# projeto_1_5.net
KiCad netlist of a schematic drawn in EAGLE
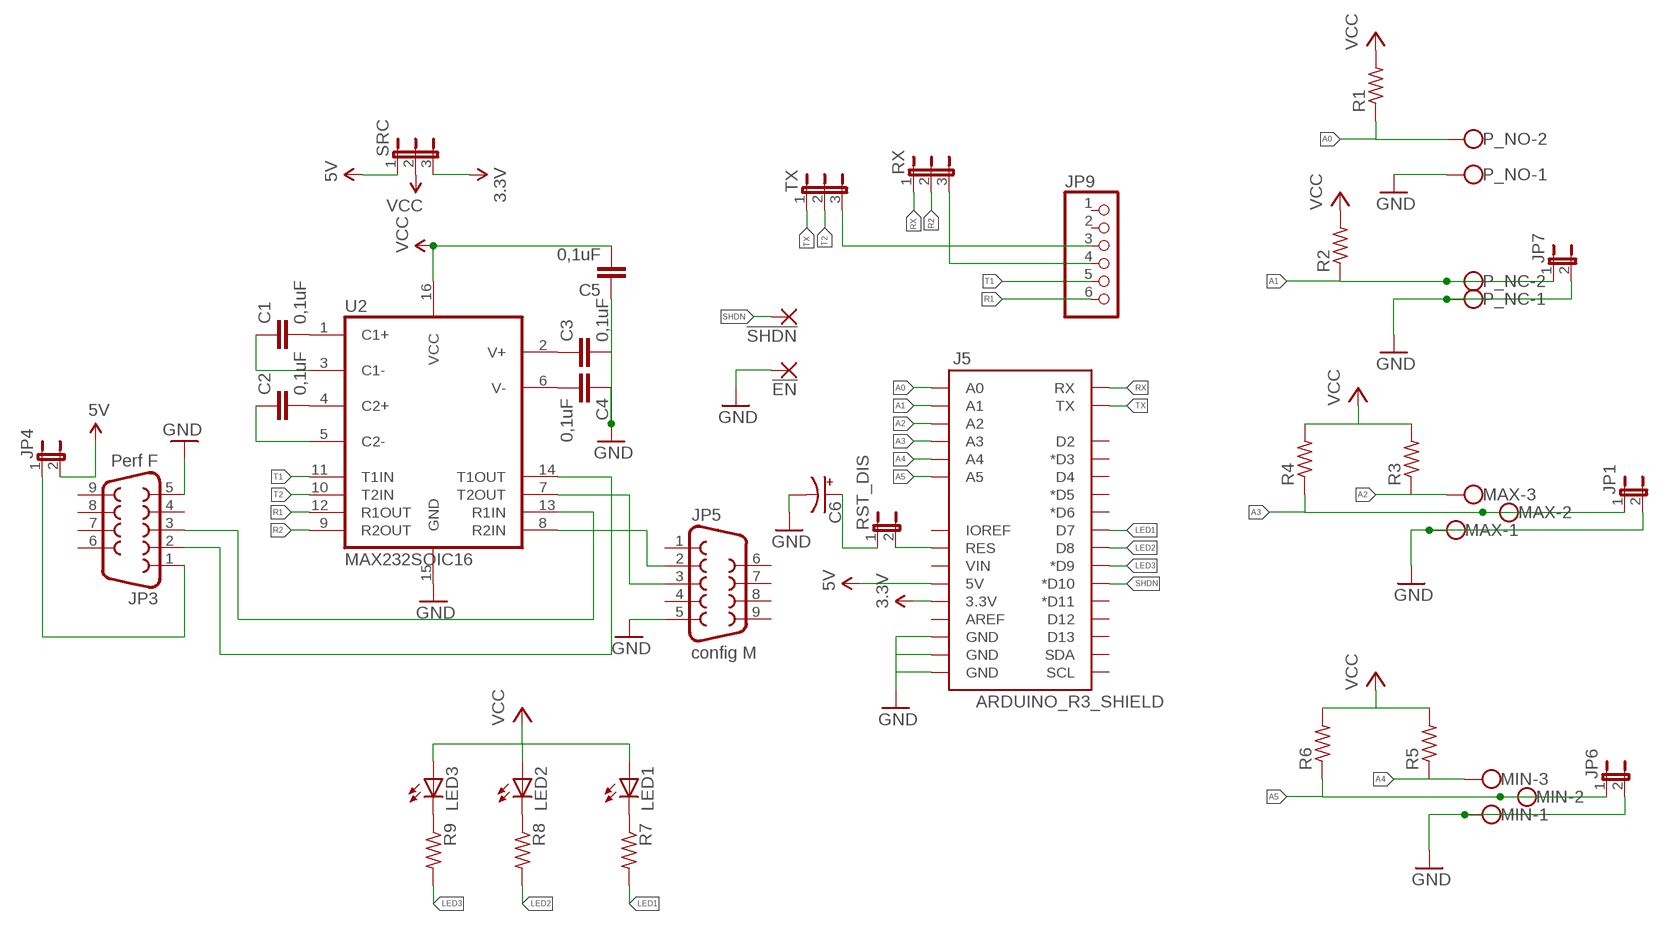
[diagram p0: schematic, sheet 1]

(export (version "E")
  (design (tool "Eeschema 10.0.6"))
  (components
    (comp (ref "!EN")
      (value "SMD2")
      (footprint "eagle-import:SMD1,27-2,54")
      (libsource (lib "eagle-import") (part "SMD2"))
    )
    (comp (ref "!SHDN")
      (value "SMD2")
      (footprint "eagle-import:SMD1,27-2,54")
      (libsource (lib "eagle-import") (part "SMD2"))
    )
    (comp (ref "C1")
      (value "0,1uF")
      (footprint "eagle-import:C0805K")
      (libsource (lib "eagle-import") (part "C-EUC0805K"))
    )
    (comp (ref "C2")
      (value "0,1uF")
      (footprint "eagle-import:C0805K")
      (libsource (lib "eagle-import") (part "C-EUC0805K"))
    )
    (comp (ref "C3")
      (value "0,1uF")
      (footprint "eagle-import:C0805K")
      (libsource (lib "eagle-import") (part "C-EUC0805K"))
    )
    (comp (ref "C4")
      (value "0,1uF")
      (footprint "eagle-import:C0805K")
      (libsource (lib "eagle-import") (part "C-EUC0805K"))
    )
    (comp (ref "C5")
      (value "0,1uF")
      (footprint "eagle-import:C0805K")
      (libsource (lib "eagle-import") (part "C-EUC0805K"))
    )
    (comp (ref "C6")
      (value "CPOL-USTT5D10")
      (footprint "eagle-import:TT5D10")
      (libsource (lib "eagle-import") (part "CPOL-USTT5D10"))
    )
    (comp (ref "J5")
      (value "ARDUINO_R3_SHIELD")
      (footprint "eagle-import:UNO_R3_SHIELD")
      (libsource (lib "eagle-import") (part "ARDUINO_R3_SHIELD"))
    )
    (comp (ref "JP1")
      (value "JP1E")
      (footprint "eagle-import:JP1")
      (libsource (lib "eagle-import") (part "JP1E"))
    )
    (comp (ref "JP3")
      (value "Perf F")
      (footprint "eagle-import:DB9")
      (libsource (lib "eagle-import") (part "DB9FEMALE"))
    )
    (comp (ref "JP4")
      (value "JP1E")
      (footprint "eagle-import:JP1")
      (libsource (lib "eagle-import") (part "JP1E"))
    )
    (comp (ref "JP5")
      (value "config M")
      (footprint "eagle-import:DB9_MALE")
      (libsource (lib "eagle-import") (part "DB9MALE"))
    )
    (comp (ref "JP6")
      (value "JP1E")
      (footprint "eagle-import:JP1")
      (libsource (lib "eagle-import") (part "JP1E"))
    )
    (comp (ref "JP7")
      (value "JP1E")
      (footprint "eagle-import:JP1")
      (libsource (lib "eagle-import") (part "JP1E"))
    )
    (comp (ref "JP9")
      (value "PINHD-1X6")
      (footprint "eagle-import:1X06")
      (libsource (lib "eagle-import") (part "PINHD-1X6"))
    )
    (comp (ref "LED1")
      (value "LED3MM")
      (footprint "eagle-import:LED3MM")
      (libsource (lib "eagle-import") (part "LED3MM"))
    )
    (comp (ref "LED2")
      (value "LED3MM")
      (footprint "eagle-import:LED3MM")
      (libsource (lib "eagle-import") (part "LED3MM"))
    )
    (comp (ref "LED3")
      (value "LED3MM")
      (footprint "eagle-import:LED3MM")
      (libsource (lib "eagle-import") (part "LED3MM"))
    )
    (comp (ref "MAX")
      (value "W237-103")
      (footprint "eagle-import:W237-103")
      (fields (field (name "MPN") "237-103"))
      (libsource (lib "eagle-import") (part "W237-103"))
    )
    (comp (ref "MIN")
      (value "W237-103")
      (footprint "eagle-import:W237-103")
      (fields (field (name "MPN") "237-103"))
      (libsource (lib "eagle-import") (part "W237-103"))
    )
    (comp (ref "P_NC")
      (value "W237-102")
      (footprint "eagle-import:W237-102")
      (fields (field (name "MPN") "237-102"))
      (libsource (lib "eagle-import") (part "W237-102"))
    )
    (comp (ref "P_NO")
      (value "W237-102")
      (footprint "eagle-import:W237-102")
      (fields (field (name "MPN") "237-102"))
      (libsource (lib "eagle-import") (part "W237-102"))
    )
    (comp (ref "R1")
      (value "R-US_R0805")
      (footprint "eagle-import:R0805")
      (libsource (lib "eagle-import") (part "R-US_R0805"))
    )
    (comp (ref "R2")
      (value "R-US_R0805")
      (footprint "eagle-import:R0805")
      (libsource (lib "eagle-import") (part "R-US_R0805"))
    )
    (comp (ref "R3")
      (value "R-US_R0805")
      (footprint "eagle-import:R0805")
      (libsource (lib "eagle-import") (part "R-US_R0805"))
    )
    (comp (ref "R4")
      (value "R-US_R0805")
      (footprint "eagle-import:R0805")
      (libsource (lib "eagle-import") (part "R-US_R0805"))
    )
    (comp (ref "R5")
      (value "R-US_R0805")
      (footprint "eagle-import:R0805")
      (libsource (lib "eagle-import") (part "R-US_R0805"))
    )
    (comp (ref "R6")
      (value "R-US_R0805")
      (footprint "eagle-import:R0805")
      (libsource (lib "eagle-import") (part "R-US_R0805"))
    )
    (comp (ref "R7")
      (value "R-US_R0805")
      (footprint "eagle-import:R0805")
      (libsource (lib "eagle-import") (part "R-US_R0805"))
    )
    (comp (ref "R8")
      (value "R-US_R0805")
      (footprint "eagle-import:R0805")
      (libsource (lib "eagle-import") (part "R-US_R0805"))
    )
    (comp (ref "R9")
      (value "R-US_R0805")
      (footprint "eagle-import:R0805")
      (libsource (lib "eagle-import") (part "R-US_R0805"))
    )
    (comp (ref "RST_DIS")
      (value "JP1E")
      (footprint "eagle-import:JP1")
      (libsource (lib "eagle-import") (part "JP1E"))
    )
    (comp (ref "RX")
      (value "JP2W")
      (footprint "eagle-import:JP2W")
      (libsource (lib "eagle-import") (part "JP2W"))
    )
    (comp (ref "SRC")
      (value "JP2W")
      (footprint "eagle-import:JP2W")
      (libsource (lib "eagle-import") (part "JP2W"))
    )
    (comp (ref "TX")
      (value "JP2W")
      (footprint "eagle-import:JP2W")
      (libsource (lib "eagle-import") (part "JP2W"))
    )
    (comp (ref "U2")
      (value "MAX232SOIC16")
      (footprint "eagle-import:SO016")
      (libsource (lib "eagle-import") (part "MAX232SOIC16"))
    )
  )
  (nets
    (net (code "1") (name "3.3V") (class "Default")
      (node (ref "J5") (pin "3.3V") (pinfunction "3.3V_3.3V") (pintype "bidirectional"))
      (node (ref "SRC") (pin "3") (pinfunction "3_3") (pintype "passive"))
    )
    (net (code "2") (name "5V") (class "Default")
      (node (ref "J5") (pin "5V") (pinfunction "5V_5V") (pintype "bidirectional"))
      (node (ref "JP4") (pin "2") (pinfunction "2_2") (pintype "passive"))
      (node (ref "SRC") (pin "1") (pinfunction "1_1") (pintype "passive"))
    )
    (net (code "3") (name "A0") (class "Default")
      (node (ref "J5") (pin "A0") (pinfunction "A0_A0") (pintype "bidirectional"))
      (node (ref "P_NO") (pin "2") (pinfunction "KL_2") (pintype "passive"))
      (node (ref "R1") (pin "1") (pinfunction "1_1") (pintype "passive"))
    )
    (net (code "4") (name "A1") (class "Default")
      (node (ref "J5") (pin "A1") (pinfunction "A1_A1") (pintype "bidirectional"))
      (node (ref "JP7") (pin "1") (pinfunction "1_1") (pintype "passive"))
      (node (ref "P_NC") (pin "2") (pinfunction "KL_2") (pintype "passive"))
      (node (ref "R2") (pin "1") (pinfunction "1_1") (pintype "passive"))
    )
    (net (code "5") (name "A2") (class "Default")
      (node (ref "J5") (pin "A2") (pinfunction "A2_A2") (pintype "bidirectional"))
      (node (ref "MAX") (pin "3") (pinfunction "KL_3") (pintype "passive"))
      (node (ref "R3") (pin "1") (pinfunction "1_1") (pintype "passive"))
    )
    (net (code "6") (name "A3") (class "Default")
      (node (ref "J5") (pin "A3") (pinfunction "A3_A3") (pintype "bidirectional"))
      (node (ref "JP1") (pin "1") (pinfunction "1_1") (pintype "passive"))
      (node (ref "MAX") (pin "2") (pinfunction "KL_2") (pintype "passive"))
      (node (ref "R4") (pin "1") (pinfunction "1_1") (pintype "passive"))
    )
    (net (code "7") (name "A4") (class "Default")
      (node (ref "J5") (pin "A4") (pinfunction "A4_A4") (pintype "bidirectional"))
      (node (ref "MIN") (pin "3") (pinfunction "KL_3") (pintype "passive"))
      (node (ref "R5") (pin "1") (pinfunction "1_1") (pintype "passive"))
    )
    (net (code "8") (name "A5") (class "Default")
      (node (ref "J5") (pin "A5") (pinfunction "A5_A5") (pintype "bidirectional"))
      (node (ref "JP6") (pin "1") (pinfunction "1_1") (pintype "passive"))
      (node (ref "MIN") (pin "2") (pinfunction "KL_2") (pintype "passive"))
      (node (ref "R6") (pin "1") (pinfunction "1_1") (pintype "passive"))
    )
    (net (code "9") (name "GND") (class "Default")
      (node (ref "!EN") (pin "1") (pinfunction "P_1") (pintype "passive"))
      (node (ref "C3") (pin "2") (pinfunction "2_2") (pintype "passive"))
      (node (ref "C4") (pin "1") (pinfunction "1_1") (pintype "passive"))
      (node (ref "C5") (pin "1") (pinfunction "1_1") (pintype "passive"))
      (node (ref "C6") (pin "-") (pinfunction "-_-") (pintype "passive"))
      (node (ref "J5") (pin "GND@0") (pinfunction "GND_GND@0") (pintype "bidirectional"))
      (node (ref "J5") (pin "GND@1") (pinfunction "GND_GND@1") (pintype "bidirectional"))
      (node (ref "J5") (pin "GND@2") (pinfunction "GND_GND@2") (pintype "bidirectional"))
      (node (ref "JP1") (pin "2") (pinfunction "2_2") (pintype "passive"))
      (node (ref "JP3") (pin "5") (pinfunction "5_5") (pintype "passive"))
      (node (ref "JP5") (pin "5") (pinfunction "5_5") (pintype "passive"))
      (node (ref "JP6") (pin "2") (pinfunction "2_2") (pintype "passive"))
      (node (ref "JP7") (pin "2") (pinfunction "2_2") (pintype "passive"))
      (node (ref "MAX") (pin "1") (pinfunction "KL_1") (pintype "passive"))
      (node (ref "MIN") (pin "1") (pinfunction "KL_1") (pintype "passive"))
      (node (ref "P_NC") (pin "1") (pinfunction "KL_1") (pintype "passive"))
      (node (ref "P_NO") (pin "1") (pinfunction "KL_1") (pintype "passive"))
      (node (ref "U2") (pin "15") (pinfunction "GND_15") (pintype "bidirectional"))
    )
    (net (code "10") (name "LED1") (class "Default")
      (node (ref "J5") (pin "D7") (pinfunction "D7_D7") (pintype "bidirectional"))
      (node (ref "R7") (pin "2") (pinfunction "2_2") (pintype "passive"))
    )
    (net (code "11") (name "LED2") (class "Default")
      (node (ref "J5") (pin "D8") (pinfunction "D8_D8") (pintype "bidirectional"))
      (node (ref "R8") (pin "2") (pinfunction "2_2") (pintype "passive"))
    )
    (net (code "12") (name "LED3") (class "Default")
      (node (ref "J5") (pin "D9") (pinfunction "*D9_D9") (pintype "bidirectional"))
      (node (ref "R9") (pin "2") (pinfunction "2_2") (pintype "passive"))
    )
    (net (code "13") (name "Net-(C6-Pad+)") (class "Default")
      (node (ref "C6") (pin "+") (pinfunction "+_+") (pintype "passive"))
      (node (ref "RST_DIS") (pin "1") (pinfunction "1_1") (pintype "passive"))
    )
    (net (code "14") (name "Net-(J5-PadRES)") (class "Default")
      (node (ref "J5") (pin "RES") (pinfunction "RES_RES") (pintype "bidirectional"))
      (node (ref "RST_DIS") (pin "2") (pinfunction "2_2") (pintype "passive"))
    )
    (net (code "15") (name "Net-(JP3-Pad1)") (class "Default")
      (node (ref "JP3") (pin "1") (pinfunction "1_1") (pintype "passive"))
      (node (ref "JP4") (pin "1") (pinfunction "1_1") (pintype "passive"))
    )
    (net (code "16") (name "Net-(JP9-Pad3)") (class "Default")
      (node (ref "JP9") (pin "3") (pinfunction "3_3") (pintype "passive"))
      (node (ref "TX") (pin "3") (pinfunction "3_3") (pintype "passive"))
    )
    (net (code "17") (name "Net-(JP9-Pad4)") (class "Default")
      (node (ref "JP9") (pin "4") (pinfunction "4_4") (pintype "passive"))
      (node (ref "RX") (pin "3") (pinfunction "3_3") (pintype "passive"))
    )
    (net (code "18") (name "Net-(LED1-C)") (class "Default")
      (node (ref "LED1") (pin "K") (pinfunction "C_K") (pintype "passive"))
      (node (ref "R7") (pin "1") (pinfunction "1_1") (pintype "passive"))
    )
    (net (code "19") (name "Net-(LED2-C)") (class "Default")
      (node (ref "LED2") (pin "K") (pinfunction "C_K") (pintype "passive"))
      (node (ref "R8") (pin "1") (pinfunction "1_1") (pintype "passive"))
    )
    (net (code "20") (name "Net-(LED3-C)") (class "Default")
      (node (ref "LED3") (pin "K") (pinfunction "C_K") (pintype "passive"))
      (node (ref "R9") (pin "1") (pinfunction "1_1") (pintype "passive"))
    )
    (net (code "21") (name "Net-(U2-C1+)") (class "Default")
      (node (ref "C1") (pin "2") (pinfunction "2_2") (pintype "passive"))
      (node (ref "U2") (pin "1") (pinfunction "C1+_1") (pintype "bidirectional"))
    )
    (net (code "22") (name "Net-(U2-C1-)") (class "Default")
      (node (ref "C1") (pin "1") (pinfunction "1_1") (pintype "passive"))
      (node (ref "U2") (pin "3") (pinfunction "C1-_3") (pintype "bidirectional"))
    )
    (net (code "23") (name "Net-(U2-C2+)") (class "Default")
      (node (ref "C2") (pin "2") (pinfunction "2_2") (pintype "passive"))
      (node (ref "U2") (pin "4") (pinfunction "C2+_4") (pintype "bidirectional"))
    )
    (net (code "24") (name "Net-(U2-C2-)") (class "Default")
      (node (ref "C2") (pin "1") (pinfunction "1_1") (pintype "passive"))
      (node (ref "U2") (pin "5") (pinfunction "C2-_5") (pintype "bidirectional"))
    )
    (net (code "25") (name "Net-(U2-R1IN)") (class "Default")
      (node (ref "JP3") (pin "3") (pinfunction "3_3") (pintype "passive"))
      (node (ref "U2") (pin "13") (pinfunction "R1IN_13") (pintype "input"))
    )
    (net (code "26") (name "Net-(U2-R2IN)") (class "Default")
      (node (ref "JP5") (pin "2") (pinfunction "2_2") (pintype "passive"))
      (node (ref "U2") (pin "8") (pinfunction "R2IN_8") (pintype "input"))
    )
    (net (code "27") (name "Net-(U2-T1OUT)") (class "Default")
      (node (ref "JP3") (pin "2") (pinfunction "2_2") (pintype "passive"))
      (node (ref "U2") (pin "14") (pinfunction "T1OUT_14") (pintype "output"))
    )
    (net (code "28") (name "Net-(U2-T2OUT)") (class "Default")
      (node (ref "JP5") (pin "3") (pinfunction "3_3") (pintype "passive"))
      (node (ref "U2") (pin "7") (pinfunction "T2OUT_7") (pintype "output"))
    )
    (net (code "29") (name "Net-(U2-V+)") (class "Default")
      (node (ref "C3") (pin "1") (pinfunction "1_1") (pintype "passive"))
      (node (ref "U2") (pin "2") (pinfunction "V+_2") (pintype "bidirectional"))
    )
    (net (code "30") (name "Net-(U2-V-)") (class "Default")
      (node (ref "C4") (pin "2") (pinfunction "2_2") (pintype "passive"))
      (node (ref "U2") (pin "6") (pinfunction "V-_6") (pintype "bidirectional"))
    )
    (net (code "31") (name "R1") (class "Default")
      (node (ref "JP9") (pin "6") (pinfunction "6_6") (pintype "passive"))
      (node (ref "U2") (pin "12") (pinfunction "R1OUT_12") (pintype "output"))
    )
    (net (code "32") (name "R2") (class "Default")
      (node (ref "RX") (pin "2") (pinfunction "2_2") (pintype "passive"))
      (node (ref "U2") (pin "9") (pinfunction "R2OUT_9") (pintype "output"))
    )
    (net (code "33") (name "RX") (class "Default")
      (node (ref "J5") (pin "RX") (pinfunction "RX_RX") (pintype "bidirectional"))
      (node (ref "RX") (pin "1") (pinfunction "1_1") (pintype "passive"))
    )
    (net (code "34") (name "SHDN") (class "Default")
      (node (ref "!SHDN") (pin "1") (pinfunction "P_1") (pintype "passive"))
      (node (ref "J5") (pin "D10") (pinfunction "*D10_D10") (pintype "bidirectional"))
    )
    (net (code "35") (name "T1") (class "Default")
      (node (ref "JP9") (pin "5") (pinfunction "5_5") (pintype "passive"))
      (node (ref "U2") (pin "11") (pinfunction "T1IN_11") (pintype "input"))
    )
    (net (code "36") (name "T2") (class "Default")
      (node (ref "TX") (pin "2") (pinfunction "2_2") (pintype "passive"))
      (node (ref "U2") (pin "10") (pinfunction "T2IN_10") (pintype "input"))
    )
    (net (code "37") (name "TX") (class "Default")
      (node (ref "J5") (pin "TX") (pinfunction "TX_TX") (pintype "bidirectional"))
      (node (ref "TX") (pin "1") (pinfunction "1_1") (pintype "passive"))
    )
    (net (code "38") (name "VCC") (class "Default")
      (node (ref "C5") (pin "2") (pinfunction "2_2") (pintype "passive"))
      (node (ref "LED1") (pin "A") (pinfunction "A_A") (pintype "passive"))
      (node (ref "LED2") (pin "A") (pinfunction "A_A") (pintype "passive"))
      (node (ref "LED3") (pin "A") (pinfunction "A_A") (pintype "passive"))
      (node (ref "R1") (pin "2") (pinfunction "2_2") (pintype "passive"))
      (node (ref "R2") (pin "2") (pinfunction "2_2") (pintype "passive"))
      (node (ref "R3") (pin "2") (pinfunction "2_2") (pintype "passive"))
      (node (ref "R4") (pin "2") (pinfunction "2_2") (pintype "passive"))
      (node (ref "R5") (pin "2") (pinfunction "2_2") (pintype "passive"))
      (node (ref "R6") (pin "2") (pinfunction "2_2") (pintype "passive"))
      (node (ref "SRC") (pin "2") (pinfunction "2_2") (pintype "passive"))
      (node (ref "U2") (pin "16") (pinfunction "VCC_16") (pintype "bidirectional"))
    )
    (net (code "39") (name "unconnected-(J5-*D3-PadD3)") (class "Default")
      (node (ref "J5") (pin "D3") (pinfunction "*D3_D3") (pintype "bidirectional"))
    )
    (net (code "40") (name "unconnected-(J5-*D5-PadD5)") (class "Default")
      (node (ref "J5") (pin "D5") (pinfunction "*D5_D5") (pintype "bidirectional"))
    )
    (net (code "41") (name "unconnected-(J5-*D6-PadD6)") (class "Default")
      (node (ref "J5") (pin "D6") (pinfunction "*D6_D6") (pintype "bidirectional"))
    )
    (net (code "42") (name "unconnected-(J5-*D11-PadD11)") (class "Default")
      (node (ref "J5") (pin "D11") (pinfunction "*D11_D11") (pintype "bidirectional"))
    )
    (net (code "43") (name "unconnected-(J5-PadAREF)") (class "Default")
      (node (ref "J5") (pin "AREF") (pinfunction "AREF_AREF") (pintype "bidirectional"))
    )
    (net (code "44") (name "unconnected-(J5-PadD2)") (class "Default")
      (node (ref "J5") (pin "D2") (pinfunction "D2_D2") (pintype "bidirectional"))
    )
    (net (code "45") (name "unconnected-(J5-PadD4)") (class "Default")
      (node (ref "J5") (pin "D4") (pinfunction "D4_D4") (pintype "bidirectional"))
    )
    (net (code "46") (name "unconnected-(J5-PadD12)") (class "Default")
      (node (ref "J5") (pin "D12") (pinfunction "D12_D12") (pintype "bidirectional"))
    )
    (net (code "47") (name "unconnected-(J5-PadD13)") (class "Default")
      (node (ref "J5") (pin "D13") (pinfunction "D13_D13") (pintype "bidirectional"))
    )
    (net (code "48") (name "unconnected-(J5-PadIOREF)") (class "Default")
      (node (ref "J5") (pin "IOREF") (pinfunction "IOREF_IOREF") (pintype "bidirectional"))
    )
    (net (code "49") (name "unconnected-(J5-PadSCL)") (class "Default")
      (node (ref "J5") (pin "SCL") (pinfunction "SCL_SCL") (pintype "bidirectional"))
    )
    (net (code "50") (name "unconnected-(J5-PadSDA)") (class "Default")
      (node (ref "J5") (pin "SDA") (pinfunction "SDA_SDA") (pintype "bidirectional"))
    )
    (net (code "51") (name "unconnected-(J5-PadVIN)") (class "Default")
      (node (ref "J5") (pin "VIN") (pinfunction "VIN_VIN") (pintype "bidirectional"))
    )
    (net (code "52") (name "unconnected-(JP3-Pad4)") (class "Default")
      (node (ref "JP3") (pin "4") (pinfunction "4_4") (pintype "passive"))
    )
    (net (code "53") (name "unconnected-(JP3-Pad6)") (class "Default")
      (node (ref "JP3") (pin "6") (pinfunction "6_6") (pintype "passive"))
    )
    (net (code "54") (name "unconnected-(JP3-Pad7)") (class "Default")
      (node (ref "JP3") (pin "7") (pinfunction "7_7") (pintype "passive"))
    )
    (net (code "55") (name "unconnected-(JP3-Pad8)") (class "Default")
      (node (ref "JP3") (pin "8") (pinfunction "8_8") (pintype "passive"))
    )
    (net (code "56") (name "unconnected-(JP3-Pad9)") (class "Default")
      (node (ref "JP3") (pin "9") (pinfunction "9_9") (pintype "passive"))
    )
    (net (code "57") (name "unconnected-(JP5-Pad1)") (class "Default")
      (node (ref "JP5") (pin "1") (pinfunction "1_1") (pintype "passive"))
    )
    (net (code "58") (name "unconnected-(JP5-Pad4)") (class "Default")
      (node (ref "JP5") (pin "4") (pinfunction "4_4") (pintype "passive"))
    )
    (net (code "59") (name "unconnected-(JP5-Pad6)") (class "Default")
      (node (ref "JP5") (pin "6") (pinfunction "6_6") (pintype "passive"))
    )
    (net (code "60") (name "unconnected-(JP5-Pad7)") (class "Default")
      (node (ref "JP5") (pin "7") (pinfunction "7_7") (pintype "passive"))
    )
    (net (code "61") (name "unconnected-(JP5-Pad8)") (class "Default")
      (node (ref "JP5") (pin "8") (pinfunction "8_8") (pintype "passive"))
    )
    (net (code "62") (name "unconnected-(JP5-Pad9)") (class "Default")
      (node (ref "JP5") (pin "9") (pinfunction "9_9") (pintype "passive"))
    )
    (net (code "63") (name "unconnected-(JP9-Pad1)") (class "Default")
      (node (ref "JP9") (pin "1") (pinfunction "1_1") (pintype "passive"))
    )
    (net (code "64") (name "unconnected-(JP9-Pad2)") (class "Default")
      (node (ref "JP9") (pin "2") (pinfunction "2_2") (pintype "passive"))
    )
  )
)
